# mainboard.net
KiCad netlist of a schematic drawn in EAGLE
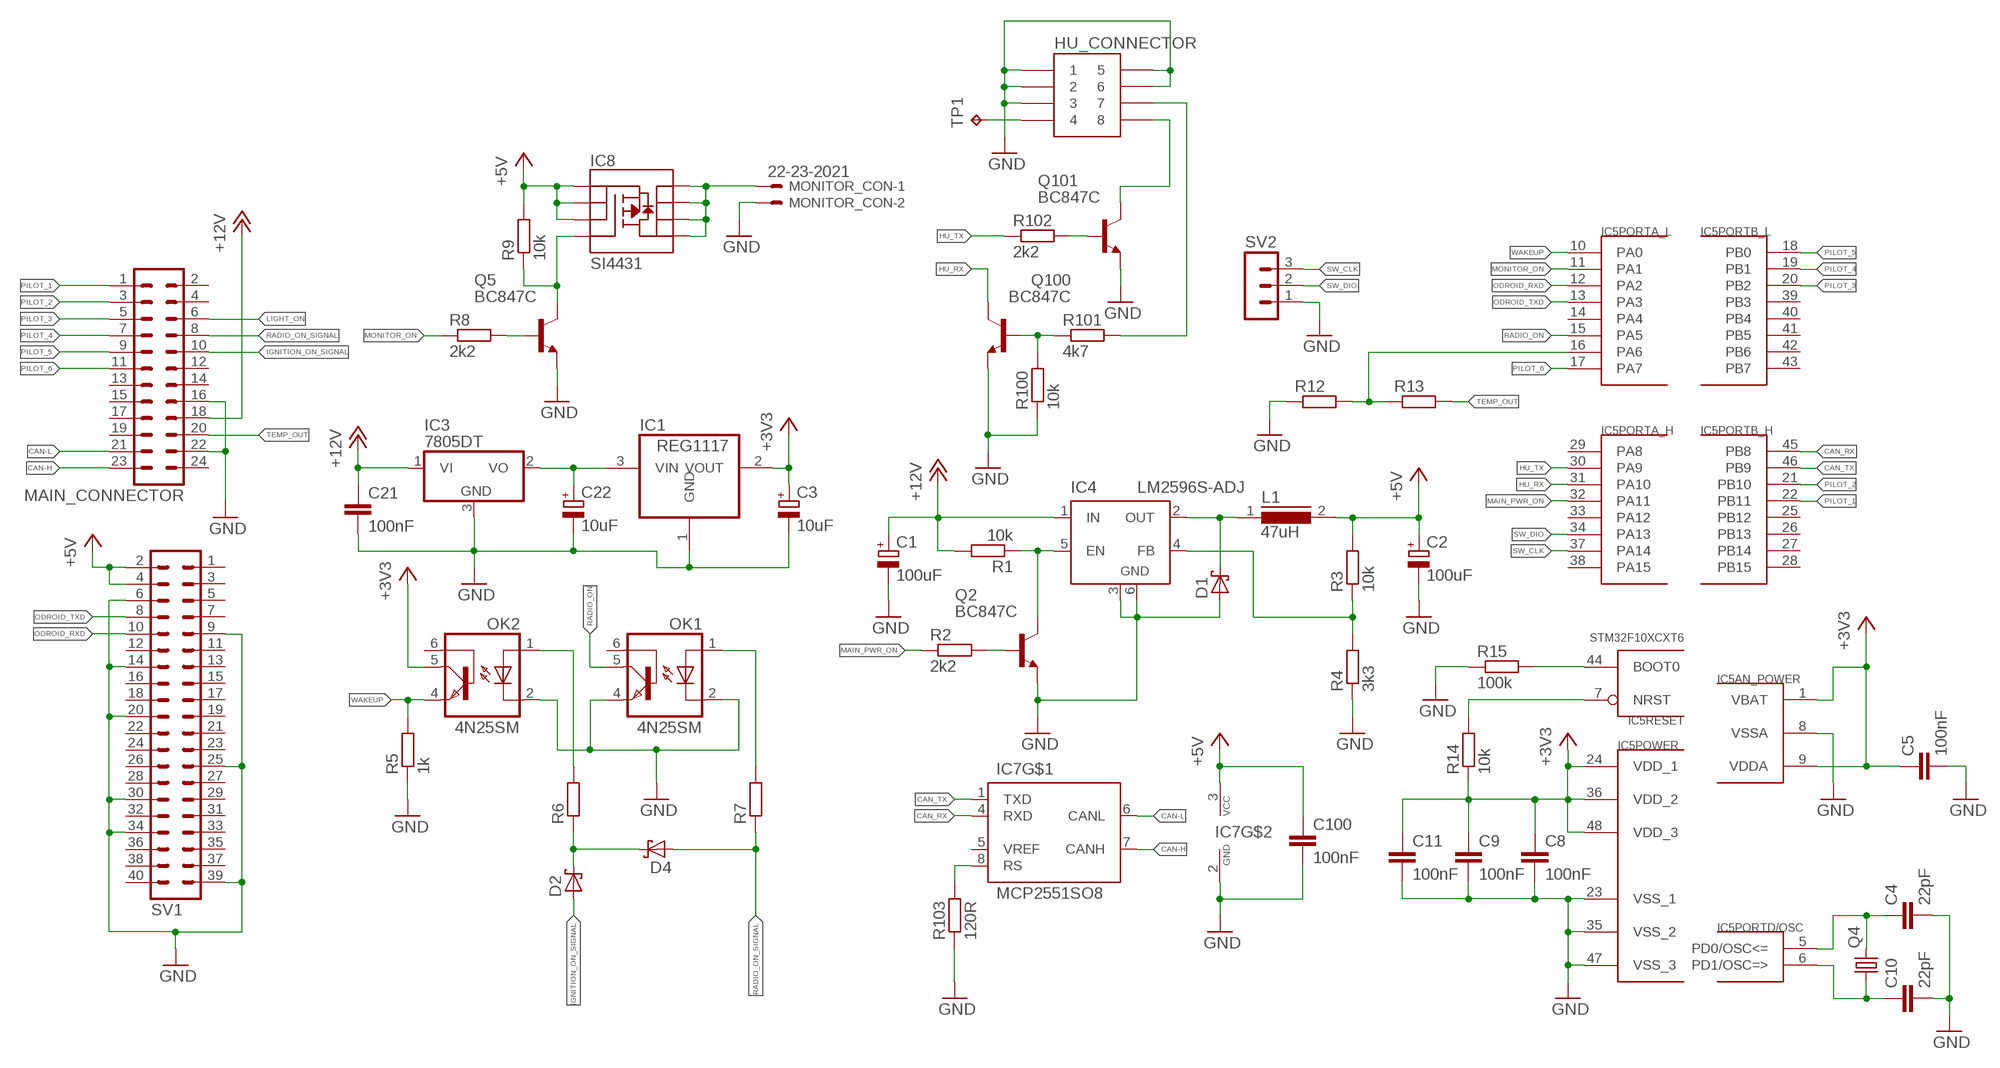
[diagram p0: schematic, sheet 1]

(export (version "E")
  (design (tool "Eeschema 10.0.6"))
  (components
    (comp (ref "C1")
      (value "100uF")
      (footprint "eagle-import:153CLV-0807")
      (libsource (lib "eagle-import") (part "CPOL-EU153CLV-0807"))
    )
    (comp (ref "C2")
      (value "100uF")
      (footprint "eagle-import:153CLV-0807")
      (libsource (lib "eagle-import") (part "CPOL-EU153CLV-0807"))
    )
    (comp (ref "C3")
      (value "10uF")
      (footprint "eagle-import:SMC_A")
      (libsource (lib "eagle-import") (part "CPOL-EUSMCA"))
    )
    (comp (ref "C4")
      (value "22pF")
      (footprint "eagle-import:C0805")
      (libsource (lib "eagle-import") (part "C-EUC0805"))
    )
    (comp (ref "C5")
      (value "100nF")
      (footprint "eagle-import:C0603")
      (libsource (lib "eagle-import") (part "C-EUC0603"))
    )
    (comp (ref "C8")
      (value "100nF")
      (footprint "eagle-import:C0805")
      (libsource (lib "eagle-import") (part "C-EUC0805"))
    )
    (comp (ref "C9")
      (value "100nF")
      (footprint "eagle-import:C0805")
      (libsource (lib "eagle-import") (part "C-EUC0805"))
    )
    (comp (ref "C10")
      (value "22pF")
      (footprint "eagle-import:C0805")
      (libsource (lib "eagle-import") (part "C-EUC0805"))
    )
    (comp (ref "C11")
      (value "100nF")
      (footprint "eagle-import:C0805")
      (libsource (lib "eagle-import") (part "C-EUC0805"))
    )
    (comp (ref "C21")
      (value "100nF")
      (footprint "eagle-import:C0805")
      (libsource (lib "eagle-import") (part "C-EUC0805"))
    )
    (comp (ref "C22")
      (value "10uF")
      (footprint "eagle-import:SMC_A")
      (libsource (lib "eagle-import") (part "CPOL-EUSMCA"))
    )
    (comp (ref "C100")
      (value "100nF")
      (footprint "eagle-import:C0805")
      (libsource (lib "eagle-import") (part "C-EUC0805"))
    )
    (comp (ref "D1")
      (value "SCHOTTKY-DIODESMD")
      (footprint "eagle-import:SMB")
      (libsource (lib "eagle-import") (part "SCHOTTKY-DIODESMD"))
    )
    (comp (ref "D2")
      (value "SCHOTTKY-DIODESMD")
      (footprint "eagle-import:SMB")
      (libsource (lib "eagle-import") (part "SCHOTTKY-DIODESMD"))
    )
    (comp (ref "D4")
      (value "SCHOTTKY-DIODESMD")
      (footprint "eagle-import:SMB")
      (libsource (lib "eagle-import") (part "SCHOTTKY-DIODESMD"))
    )
    (comp (ref "HU_CONNECTOR")
      (value "MRX56908CV")
      (footprint "eagle-import:MRX56908")
      (libsource (lib "eagle-import") (part "MRX56908CV"))
    )
    (comp (ref "IC1")
      (value "REG1117")
      (footprint "eagle-import:SOT223")
      (libsource (lib "eagle-import") (part "REG1117"))
    )
    (comp (ref "IC3")
      (value "7805DT")
      (footprint "eagle-import:TO252")
      (libsource (lib "eagle-import") (part "78DT05"))
    )
    (comp (ref "IC4")
      (value "LM2596S-ADJ")
      (footprint "eagle-import:TO263-5")
      (libsource (lib "eagle-import") (part "LM2596S"))
    )
    (comp (ref "IC5")
      (value "STM32F10XCXT6")
      (footprint "eagle-import:TQFP48")
      (libsource (lib "eagle-import") (part "STM32F10XCXT6"))
    )
    (comp (ref "IC7")
      (value "MCP2551SO8")
      (footprint "eagle-import:SO08")
      (libsource (lib "eagle-import") (part "MCP2551SO8"))
    )
    (comp (ref "IC8")
      (value "SI4431")
      (footprint "eagle-import:SO08")
      (libsource (lib "eagle-import") (part "MOSFET-PCHANNEL-SOIC8SOIC8"))
    )
    (comp (ref "L1")
      (value "47uH")
      (footprint "eagle-import:DR125")
      (libsource (lib "eagle-import") (part "DR125"))
    )
    (comp (ref "MAIN_CONNECTOR")
      (value "MA12-2")
      (footprint "eagle-import:MA12-2")
      (libsource (lib "eagle-import") (part "MA12-2"))
    )
    (comp (ref "MONITOR_CON")
      (value "22-23-2021")
      (footprint "eagle-import:22-23-2021")
      (libsource (lib "eagle-import") (part "22-23-2021"))
    )
    (comp (ref "OK1")
      (value "4N25SM")
      (footprint "eagle-import:DIL6-SMD")
      (libsource (lib "eagle-import") (part "4N?MS25"))
    )
    (comp (ref "OK2")
      (value "4N25SM")
      (footprint "eagle-import:DIL6-SMD")
      (libsource (lib "eagle-import") (part "4N?MS25"))
    )
    (comp (ref "Q2")
      (value "BC847C")
      (footprint "eagle-import:SOT23-BEC")
      (libsource (lib "eagle-import") (part "-NPN-SOT23-BECBC847C"))
    )
    (comp (ref "Q4")
      (value "CRYSTALHC49UP")
      (footprint "eagle-import:HC49UP")
      (libsource (lib "eagle-import") (part "CRYSTALHC49UP"))
    )
    (comp (ref "Q5")
      (value "BC847C")
      (footprint "eagle-import:SOT23-BEC")
      (libsource (lib "eagle-import") (part "-NPN-SOT23-BECBC847C"))
    )
    (comp (ref "Q100")
      (value "BC847C")
      (footprint "eagle-import:SOT23-BEC")
      (libsource (lib "eagle-import") (part "-NPN-SOT23-BECBC847C"))
    )
    (comp (ref "Q101")
      (value "BC847C")
      (footprint "eagle-import:SOT23-BEC")
      (libsource (lib "eagle-import") (part "-NPN-SOT23-BECBC847C"))
    )
    (comp (ref "R1")
      (value "10k")
      (footprint "eagle-import:M0805")
      (libsource (lib "eagle-import") (part "R-EU_M0805"))
    )
    (comp (ref "R2")
      (value "2k2")
      (footprint "eagle-import:M0805")
      (libsource (lib "eagle-import") (part "R-EU_M0805"))
    )
    (comp (ref "R3")
      (value "10k")
      (footprint "eagle-import:M0805")
      (libsource (lib "eagle-import") (part "R-EU_M0805"))
    )
    (comp (ref "R4")
      (value "3k3")
      (footprint "eagle-import:M0805")
      (libsource (lib "eagle-import") (part "R-EU_M0805"))
    )
    (comp (ref "R5")
      (value "1k")
      (footprint "eagle-import:M0805")
      (libsource (lib "eagle-import") (part "R-EU_M0805"))
    )
    (comp (ref "R6")
      (value "R-EU_M0805")
      (footprint "eagle-import:M0805")
      (libsource (lib "eagle-import") (part "R-EU_M0805"))
    )
    (comp (ref "R7")
      (value "R-EU_M0805")
      (footprint "eagle-import:M0805")
      (libsource (lib "eagle-import") (part "R-EU_M0805"))
    )
    (comp (ref "R8")
      (value "2k2")
      (footprint "eagle-import:M0805")
      (libsource (lib "eagle-import") (part "R-EU_M0805"))
    )
    (comp (ref "R9")
      (value "10k")
      (footprint "eagle-import:M0805")
      (libsource (lib "eagle-import") (part "R-EU_M0805"))
    )
    (comp (ref "R12")
      (value "R-EU_M0805")
      (footprint "eagle-import:M0805")
      (libsource (lib "eagle-import") (part "R-EU_M0805"))
    )
    (comp (ref "R13")
      (value "R-EU_M0805")
      (footprint "eagle-import:M0805")
      (libsource (lib "eagle-import") (part "R-EU_M0805"))
    )
    (comp (ref "R14")
      (value "10k")
      (footprint "eagle-import:M0805")
      (libsource (lib "eagle-import") (part "R-EU_M0805"))
    )
    (comp (ref "R15")
      (value "100k")
      (footprint "eagle-import:M0805")
      (libsource (lib "eagle-import") (part "R-EU_M0805"))
    )
    (comp (ref "R100")
      (value "10k")
      (footprint "eagle-import:M0805")
      (libsource (lib "eagle-import") (part "R-EU_M0805"))
    )
    (comp (ref "R101")
      (value "4k7")
      (footprint "eagle-import:M0805")
      (libsource (lib "eagle-import") (part "R-EU_M0805"))
    )
    (comp (ref "R102")
      (value "2k2")
      (footprint "eagle-import:M0805")
      (libsource (lib "eagle-import") (part "R-EU_M0805"))
    )
    (comp (ref "R103")
      (value "120R")
      (footprint "eagle-import:R0805")
      (libsource (lib "eagle-import") (part "resistor_R-EU_R0805"))
    )
    (comp (ref "SV1")
      (value "MA20-2")
      (footprint "eagle-import:MA20-2")
      (libsource (lib "eagle-import") (part "MA20-2"))
    )
    (comp (ref "SV2")
      (value "MA03-1")
      (footprint "eagle-import:MA03-1")
      (libsource (lib "eagle-import") (part "MA03-1"))
    )
    (comp (ref "TP1")
      (value "TPPAD1-13")
      (footprint "eagle-import:P1-13")
      (libsource (lib "eagle-import") (part "TPPAD1-13"))
    )
  )
  (nets
    (net (code "1") (name "+3V3") (class "Default")
      (node (ref "C11") (pin "1") (pinfunction "1_1") (pintype "passive"))
      (node (ref "C3") (pin "+") (pinfunction "+_+") (pintype "passive"))
      (node (ref "C5") (pin "1") (pinfunction "1_1") (pintype "passive"))
      (node (ref "C8") (pin "1") (pinfunction "1_1") (pintype "passive"))
      (node (ref "C9") (pin "1") (pinfunction "1_1") (pintype "passive"))
      (node (ref "IC1") (pin "2") (pinfunction "VOUT_2") (pintype "output"))
      (node (ref "IC5") (pin "1") (pinfunction "VBAT_1") (pintype "power_in"))
      (node (ref "IC5") (pin "24") (pinfunction "VDD_1_24") (pintype "power_in"))
      (node (ref "IC5") (pin "36") (pinfunction "VDD_2_36") (pintype "power_in"))
      (node (ref "IC5") (pin "48") (pinfunction "VDD_3_48") (pintype "power_in"))
      (node (ref "IC5") (pin "9") (pinfunction "VDDA_9") (pintype "power_in"))
      (node (ref "OK2") (pin "5") (pinfunction "COL_5") (pintype "passive"))
      (node (ref "R14") (pin "1") (pinfunction "1_1") (pintype "passive"))
    )
    (net (code "2") (name "+5V") (class "Default")
      (node (ref "C100") (pin "1") (pinfunction "1_1") (pintype "passive"))
      (node (ref "C2") (pin "+") (pinfunction "+_+") (pintype "passive"))
      (node (ref "IC7") (pin "3") (pinfunction "VCC_3") (pintype "power_in"))
      (node (ref "IC8") (pin "1") (pinfunction "S_1") (pintype "bidirectional"))
      (node (ref "IC8") (pin "2") (pinfunction "S_2") (pintype "bidirectional"))
      (node (ref "IC8") (pin "3") (pinfunction "S_3") (pintype "bidirectional"))
      (node (ref "L1") (pin "2") (pinfunction "2_2") (pintype "passive"))
      (node (ref "R3") (pin "2") (pinfunction "2_2") (pintype "passive"))
      (node (ref "R9") (pin "2") (pinfunction "2_2") (pintype "passive"))
      (node (ref "SV1") (pin "2") (pinfunction "2_2") (pintype "passive"))
      (node (ref "SV1") (pin "4") (pinfunction "4_4") (pintype "passive"))
    )
    (net (code "3") (name "+12V") (class "Default")
      (node (ref "C1") (pin "+") (pinfunction "+_+") (pintype "passive"))
      (node (ref "C21") (pin "1") (pinfunction "1_1") (pintype "passive"))
      (node (ref "IC3") (pin "1") (pinfunction "VI_1") (pintype "input"))
      (node (ref "IC4") (pin "1") (pinfunction "IN_1") (pintype "input"))
      (node (ref "MAIN_CONNECTOR") (pin "18") (pinfunction "18_18") (pintype "passive"))
      (node (ref "R1") (pin "2") (pinfunction "2_2") (pintype "passive"))
    )
    (net (code "4") (name "CAN-H") (class "Default")
      (node (ref "IC7") (pin "7") (pinfunction "CANH_7") (pintype "bidirectional"))
      (node (ref "MAIN_CONNECTOR") (pin "23") (pinfunction "23_23") (pintype "passive"))
    )
    (net (code "5") (name "CAN-L") (class "Default")
      (node (ref "IC7") (pin "6") (pinfunction "CANL_6") (pintype "bidirectional"))
      (node (ref "MAIN_CONNECTOR") (pin "21") (pinfunction "21_21") (pintype "passive"))
    )
    (net (code "6") (name "CAN_RX") (class "Default")
      (node (ref "IC5") (pin "45") (pinfunction "PB8_45") (pintype "bidirectional"))
      (node (ref "IC7") (pin "4") (pinfunction "RXD_4") (pintype "bidirectional"))
    )
    (net (code "7") (name "CAN_TX") (class "Default")
      (node (ref "IC5") (pin "46") (pinfunction "PB9_46") (pintype "bidirectional"))
      (node (ref "IC7") (pin "1") (pinfunction "TXD_1") (pintype "bidirectional"))
    )
    (net (code "8") (name "GND") (class "Default")
      (node (ref "C1") (pin "-") (pinfunction "-_-") (pintype "passive"))
      (node (ref "C10") (pin "2") (pinfunction "2_2") (pintype "passive"))
      (node (ref "C100") (pin "2") (pinfunction "2_2") (pintype "passive"))
      (node (ref "C11") (pin "2") (pinfunction "2_2") (pintype "passive"))
      (node (ref "C2") (pin "-") (pinfunction "-_-") (pintype "passive"))
      (node (ref "C21") (pin "2") (pinfunction "2_2") (pintype "passive"))
      (node (ref "C22") (pin "-") (pinfunction "-_-") (pintype "passive"))
      (node (ref "C3") (pin "-") (pinfunction "-_-") (pintype "passive"))
      (node (ref "C4") (pin "2") (pinfunction "2_2") (pintype "passive"))
      (node (ref "C5") (pin "2") (pinfunction "2_2") (pintype "passive"))
      (node (ref "C8") (pin "2") (pinfunction "2_2") (pintype "passive"))
      (node (ref "C9") (pin "2") (pinfunction "2_2") (pintype "passive"))
      (node (ref "D1") (pin "A") (pinfunction "A_A") (pintype "passive"))
      (node (ref "HU_CONNECTOR") (pin "P1") (pinfunction "1_P1") (pintype "bidirectional"))
      (node (ref "HU_CONNECTOR") (pin "P2") (pinfunction "2_P2") (pintype "bidirectional"))
      (node (ref "HU_CONNECTOR") (pin "P3") (pinfunction "3_P3") (pintype "bidirectional"))
      (node (ref "HU_CONNECTOR") (pin "P5") (pinfunction "5_P5") (pintype "bidirectional"))
      (node (ref "HU_CONNECTOR") (pin "P6") (pinfunction "6_P6") (pintype "bidirectional"))
      (node (ref "IC1") (pin "1") (pinfunction "GND_1") (pintype "power_in"))
      (node (ref "IC3") (pin "3") (pinfunction "GND_3") (pintype "passive"))
      (node (ref "IC4") (pin "3") (pinfunction "GND_3") (pintype "power_in"))
      (node (ref "IC4") (pin "6") (pinfunction "GND_6") (pintype "power_in"))
      (node (ref "IC5") (pin "23") (pinfunction "VSS_1_23") (pintype "power_in"))
      (node (ref "IC5") (pin "35") (pinfunction "VSS_2_35") (pintype "power_in"))
      (node (ref "IC5") (pin "47") (pinfunction "VSS_3_47") (pintype "power_in"))
      (node (ref "IC5") (pin "8") (pinfunction "VSSA_8") (pintype "power_in"))
      (node (ref "IC7") (pin "2") (pinfunction "GND_2") (pintype "power_in"))
      (node (ref "MAIN_CONNECTOR") (pin "16") (pinfunction "16_16") (pintype "passive"))
      (node (ref "MAIN_CONNECTOR") (pin "22") (pinfunction "22_22") (pintype "passive"))
      (node (ref "MONITOR_CON") (pin "2") (pinfunction "S_2") (pintype "passive"))
      (node (ref "OK1") (pin "2") (pinfunction "C_2") (pintype "passive"))
      (node (ref "OK1") (pin "4") (pinfunction "EMI_4") (pintype "passive"))
      (node (ref "OK2") (pin "2") (pinfunction "C_2") (pintype "passive"))
      (node (ref "Q100") (pin "E") (pinfunction "E_E") (pintype "passive"))
      (node (ref "Q101") (pin "E") (pinfunction "E_E") (pintype "passive"))
      (node (ref "Q2") (pin "E") (pinfunction "E_E") (pintype "passive"))
      (node (ref "Q5") (pin "E") (pinfunction "E_E") (pintype "passive"))
      (node (ref "R100") (pin "1") (pinfunction "1_1") (pintype "passive"))
      (node (ref "R103") (pin "1") (pinfunction "1_1") (pintype "passive"))
      (node (ref "R12") (pin "1") (pinfunction "1_1") (pintype "passive"))
      (node (ref "R15") (pin "1") (pinfunction "1_1") (pintype "passive"))
      (node (ref "R4") (pin "1") (pinfunction "1_1") (pintype "passive"))
      (node (ref "R5") (pin "1") (pinfunction "1_1") (pintype "passive"))
      (node (ref "SV1") (pin "14") (pinfunction "14_14") (pintype "passive"))
      (node (ref "SV1") (pin "20") (pinfunction "20_20") (pintype "passive"))
      (node (ref "SV1") (pin "25") (pinfunction "25_25") (pintype "passive"))
      (node (ref "SV1") (pin "30") (pinfunction "30_30") (pintype "passive"))
      (node (ref "SV1") (pin "34") (pinfunction "34_34") (pintype "passive"))
      (node (ref "SV1") (pin "39") (pinfunction "39_39") (pintype "passive"))
      (node (ref "SV1") (pin "6") (pinfunction "6_6") (pintype "passive"))
      (node (ref "SV1") (pin "9") (pinfunction "9_9") (pintype "passive"))
      (node (ref "SV2") (pin "1") (pinfunction "1_1") (pintype "passive"))
    )
    (net (code "9") (name "HU_RX") (class "Default")
      (node (ref "IC5") (pin "31") (pinfunction "PA10_31") (pintype "bidirectional"))
      (node (ref "Q100") (pin "C") (pinfunction "C_C") (pintype "passive"))
    )
    (net (code "10") (name "HU_TX") (class "Default")
      (node (ref "IC5") (pin "30") (pinfunction "PA9_30") (pintype "bidirectional"))
      (node (ref "R102") (pin "1") (pinfunction "1_1") (pintype "passive"))
    )
    (net (code "11") (name "IGNITION_ON_SIGNAL") (class "Default")
      (node (ref "D2") (pin "A") (pinfunction "A_A") (pintype "passive"))
      (node (ref "MAIN_CONNECTOR") (pin "10") (pinfunction "10_10") (pintype "passive"))
    )
    (net (code "12") (name "LIGHT_ON") (class "Default")
      (node (ref "MAIN_CONNECTOR") (pin "6") (pinfunction "6_6") (pintype "passive"))
    )
    (net (code "13") (name "MAIN_PWR_ON") (class "Default")
      (node (ref "IC5") (pin "32") (pinfunction "PA11_32") (pintype "bidirectional"))
      (node (ref "R2") (pin "1") (pinfunction "1_1") (pintype "passive"))
    )
    (net (code "14") (name "MONITOR_ON") (class "Default")
      (node (ref "IC5") (pin "11") (pinfunction "PA1_11") (pintype "bidirectional"))
      (node (ref "R8") (pin "1") (pinfunction "1_1") (pintype "passive"))
    )
    (net (code "15") (name "Net-(D2-PadC)") (class "Default")
      (node (ref "D2") (pin "C") (pinfunction "C_C") (pintype "passive"))
      (node (ref "D4") (pin "C") (pinfunction "C_C") (pintype "passive"))
      (node (ref "R6") (pin "1") (pinfunction "1_1") (pintype "passive"))
    )
    (net (code "16") (name "Net-(HU_CONNECTOR-4)") (class "Default")
      (node (ref "HU_CONNECTOR") (pin "P4") (pinfunction "4_P4") (pintype "bidirectional"))
      (node (ref "TP1") (pin "TP") (pinfunction "TP_TP") (pintype "input"))
    )
    (net (code "17") (name "Net-(HU_CONNECTOR-7)") (class "Default")
      (node (ref "HU_CONNECTOR") (pin "P7") (pinfunction "7_P7") (pintype "bidirectional"))
      (node (ref "R101") (pin "2") (pinfunction "2_2") (pintype "passive"))
    )
    (net (code "18") (name "Net-(HU_CONNECTOR-8)") (class "Default")
      (node (ref "HU_CONNECTOR") (pin "P8") (pinfunction "8_P8") (pintype "bidirectional"))
      (node (ref "Q101") (pin "C") (pinfunction "C_C") (pintype "passive"))
    )
    (net (code "19") (name "Net-(IC1-VIN)") (class "Default")
      (node (ref "C22") (pin "+") (pinfunction "+_+") (pintype "passive"))
      (node (ref "IC1") (pin "3") (pinfunction "VIN_3") (pintype "input"))
      (node (ref "IC3") (pin "2") (pinfunction "VO_2") (pintype "passive"))
    )
    (net (code "20") (name "Net-(IC4-EN)") (class "Default")
      (node (ref "IC4") (pin "5") (pinfunction "EN_5") (pintype "input"))
      (node (ref "Q2") (pin "C") (pinfunction "C_C") (pintype "passive"))
      (node (ref "R1") (pin "1") (pinfunction "1_1") (pintype "passive"))
    )
    (net (code "21") (name "Net-(IC4-FB)") (class "Default")
      (node (ref "IC4") (pin "4") (pinfunction "FB_4") (pintype "input"))
      (node (ref "R3") (pin "1") (pinfunction "1_1") (pintype "passive"))
      (node (ref "R4") (pin "2") (pinfunction "2_2") (pintype "passive"))
    )
    (net (code "22") (name "Net-(IC4-OUT)") (class "Default")
      (node (ref "D1") (pin "C") (pinfunction "C_C") (pintype "passive"))
      (node (ref "IC4") (pin "2") (pinfunction "OUT_2") (pintype "output"))
      (node (ref "L1") (pin "1") (pinfunction "1_1") (pintype "passive"))
    )
    (net (code "23") (name "Net-(IC5C-PA6)") (class "Default")
      (node (ref "IC5") (pin "16") (pinfunction "PA6_16") (pintype "bidirectional"))
      (node (ref "R12") (pin "2") (pinfunction "2_2") (pintype "passive"))
      (node (ref "R13") (pin "1") (pinfunction "1_1") (pintype "passive"))
    )
    (net (code "24") (name "Net-(IC5G-PD0{slash}OSC<=)") (class "Default")
      (node (ref "C4") (pin "1") (pinfunction "1_1") (pintype "passive"))
      (node (ref "IC5") (pin "5") (pinfunction "PD0/OSC<=_5") (pintype "bidirectional"))
      (node (ref "Q4") (pin "2") (pinfunction "2_2") (pintype "passive"))
    )
    (net (code "25") (name "Net-(IC5G-PD1{slash}OSC=>)") (class "Default")
      (node (ref "C10") (pin "1") (pinfunction "1_1") (pintype "passive"))
      (node (ref "IC5") (pin "6") (pinfunction "PD1/OSC=>_6") (pintype "bidirectional"))
      (node (ref "Q4") (pin "1") (pinfunction "1_1") (pintype "passive"))
    )
    (net (code "26") (name "Net-(IC5I-BOOT0)") (class "Default")
      (node (ref "IC5") (pin "44") (pinfunction "BOOT0_44") (pintype "input"))
      (node (ref "R15") (pin "2") (pinfunction "2_2") (pintype "passive"))
    )
    (net (code "27") (name "Net-(IC5I-NRST)") (class "Default")
      (node (ref "IC5") (pin "7") (pinfunction "NRST_7") (pintype "input"))
      (node (ref "R14") (pin "2") (pinfunction "2_2") (pintype "passive"))
    )
    (net (code "28") (name "Net-(IC7A-RS)") (class "Default")
      (node (ref "IC7") (pin "8") (pinfunction "RS_8") (pintype "bidirectional"))
      (node (ref "R103") (pin "2") (pinfunction "2_2") (pintype "passive"))
    )
    (net (code "29") (name "Net-(IC8-G)") (class "Default")
      (node (ref "IC8") (pin "4") (pinfunction "G_4") (pintype "bidirectional"))
      (node (ref "Q5") (pin "C") (pinfunction "C_C") (pintype "passive"))
      (node (ref "R9") (pin "1") (pinfunction "1_1") (pintype "passive"))
    )
    (net (code "30") (name "Net-(MONITOR_CONA-S)") (class "Default")
      (node (ref "IC8") (pin "5") (pinfunction "D_5") (pintype "bidirectional"))
      (node (ref "IC8") (pin "6") (pinfunction "D_6") (pintype "bidirectional"))
      (node (ref "IC8") (pin "7") (pinfunction "D_7") (pintype "bidirectional"))
      (node (ref "IC8") (pin "8") (pinfunction "D_8") (pintype "bidirectional"))
      (node (ref "MONITOR_CON") (pin "1") (pinfunction "S_1") (pintype "passive"))
    )
    (net (code "31") (name "Net-(OK1-A)") (class "Default")
      (node (ref "OK1") (pin "1") (pinfunction "A_1") (pintype "passive"))
      (node (ref "R7") (pin "2") (pinfunction "2_2") (pintype "passive"))
    )
    (net (code "32") (name "Net-(OK2-A)") (class "Default")
      (node (ref "OK2") (pin "1") (pinfunction "A_1") (pintype "passive"))
      (node (ref "R6") (pin "2") (pinfunction "2_2") (pintype "passive"))
    )
    (net (code "33") (name "Net-(Q2-PadB)") (class "Default")
      (node (ref "Q2") (pin "B") (pinfunction "B_B") (pintype "passive"))
      (node (ref "R2") (pin "2") (pinfunction "2_2") (pintype "passive"))
    )
    (net (code "34") (name "Net-(Q5-PadB)") (class "Default")
      (node (ref "Q5") (pin "B") (pinfunction "B_B") (pintype "passive"))
      (node (ref "R8") (pin "2") (pinfunction "2_2") (pintype "passive"))
    )
    (net (code "35") (name "Net-(Q100-PadB)") (class "Default")
      (node (ref "Q100") (pin "B") (pinfunction "B_B") (pintype "passive"))
      (node (ref "R100") (pin "2") (pinfunction "2_2") (pintype "passive"))
      (node (ref "R101") (pin "1") (pinfunction "1_1") (pintype "passive"))
    )
    (net (code "36") (name "Net-(Q101-PadB)") (class "Default")
      (node (ref "Q101") (pin "B") (pinfunction "B_B") (pintype "passive"))
      (node (ref "R102") (pin "2") (pinfunction "2_2") (pintype "passive"))
    )
    (net (code "37") (name "ODROID_RXD") (class "Default")
      (node (ref "IC5") (pin "12") (pinfunction "PA2_12") (pintype "bidirectional"))
      (node (ref "SV1") (pin "10") (pinfunction "10_10") (pintype "passive"))
    )
    (net (code "38") (name "ODROID_TXD") (class "Default")
      (node (ref "IC5") (pin "13") (pinfunction "PA3_13") (pintype "bidirectional"))
      (node (ref "SV1") (pin "8") (pinfunction "8_8") (pintype "passive"))
    )
    (net (code "39") (name "PILOT_1") (class "Default")
      (node (ref "IC5") (pin "22") (pinfunction "PB11_22") (pintype "bidirectional"))
      (node (ref "MAIN_CONNECTOR") (pin "1") (pinfunction "1_1") (pintype "passive"))
    )
    (net (code "40") (name "PILOT_2") (class "Default")
      (node (ref "IC5") (pin "21") (pinfunction "PB10_21") (pintype "bidirectional"))
      (node (ref "MAIN_CONNECTOR") (pin "3") (pinfunction "3_3") (pintype "passive"))
    )
    (net (code "41") (name "PILOT_3") (class "Default")
      (node (ref "IC5") (pin "20") (pinfunction "PB2_20") (pintype "bidirectional"))
      (node (ref "MAIN_CONNECTOR") (pin "5") (pinfunction "5_5") (pintype "passive"))
    )
    (net (code "42") (name "PILOT_4") (class "Default")
      (node (ref "IC5") (pin "19") (pinfunction "PB1_19") (pintype "bidirectional"))
      (node (ref "MAIN_CONNECTOR") (pin "7") (pinfunction "7_7") (pintype "passive"))
    )
    (net (code "43") (name "PILOT_5") (class "Default")
      (node (ref "IC5") (pin "18") (pinfunction "PB0_18") (pintype "bidirectional"))
      (node (ref "MAIN_CONNECTOR") (pin "9") (pinfunction "9_9") (pintype "passive"))
    )
    (net (code "44") (name "PILOT_6") (class "Default")
      (node (ref "IC5") (pin "17") (pinfunction "PA7_17") (pintype "bidirectional"))
      (node (ref "MAIN_CONNECTOR") (pin "11") (pinfunction "11_11") (pintype "passive"))
    )
    (net (code "45") (name "RADIO_ON") (class "Default")
      (node (ref "IC5") (pin "15") (pinfunction "PA5_15") (pintype "bidirectional"))
      (node (ref "OK1") (pin "5") (pinfunction "COL_5") (pintype "passive"))
    )
    (net (code "46") (name "RADIO_ON_SIGNAL") (class "Default")
      (node (ref "D4") (pin "A") (pinfunction "A_A") (pintype "passive"))
      (node (ref "MAIN_CONNECTOR") (pin "8") (pinfunction "8_8") (pintype "passive"))
      (node (ref "R7") (pin "1") (pinfunction "1_1") (pintype "passive"))
    )
    (net (code "47") (name "SW_CLK") (class "Default")
      (node (ref "IC5") (pin "37") (pinfunction "PA14_37") (pintype "bidirectional"))
      (node (ref "SV2") (pin "3") (pinfunction "3_3") (pintype "passive"))
    )
    (net (code "48") (name "SW_DIO") (class "Default")
      (node (ref "IC5") (pin "34") (pinfunction "PA13_34") (pintype "bidirectional"))
      (node (ref "SV2") (pin "2") (pinfunction "2_2") (pintype "passive"))
    )
    (net (code "49") (name "TEMP_OUT") (class "Default")
      (node (ref "MAIN_CONNECTOR") (pin "20") (pinfunction "20_20") (pintype "passive"))
      (node (ref "R13") (pin "2") (pinfunction "2_2") (pintype "passive"))
    )
    (net (code "50") (name "WAKEUP") (class "Default")
      (node (ref "IC5") (pin "10") (pinfunction "PA0_10") (pintype "bidirectional"))
      (node (ref "OK2") (pin "4") (pinfunction "EMI_4") (pintype "passive"))
      (node (ref "R5") (pin "2") (pinfunction "2_2") (pintype "passive"))
    )
    (net (code "51") (name "unconnected-(IC5B-PA8-Pad29)") (class "Default")
      (node (ref "IC5") (pin "29") (pinfunction "PA8_29") (pintype "bidirectional"))
    )
    (net (code "52") (name "unconnected-(IC5B-PA12-Pad33)") (class "Default")
      (node (ref "IC5") (pin "33") (pinfunction "PA12_33") (pintype "bidirectional"))
    )
    (net (code "53") (name "unconnected-(IC5B-PA15-Pad38)") (class "Default")
      (node (ref "IC5") (pin "38") (pinfunction "PA15_38") (pintype "bidirectional"))
    )
    (net (code "54") (name "unconnected-(IC5C-PA4-Pad14)") (class "Default")
      (node (ref "IC5") (pin "14") (pinfunction "PA4_14") (pintype "bidirectional"))
    )
    (net (code "55") (name "unconnected-(IC5D-PB12-Pad25)") (class "Default")
      (node (ref "IC5") (pin "25") (pinfunction "PB12_25") (pintype "bidirectional"))
    )
    (net (code "56") (name "unconnected-(IC5D-PB13-Pad26)") (class "Default")
      (node (ref "IC5") (pin "26") (pinfunction "PB13_26") (pintype "bidirectional"))
    )
    (net (code "57") (name "unconnected-(IC5D-PB14-Pad27)") (class "Default")
      (node (ref "IC5") (pin "27") (pinfunction "PB14_27") (pintype "bidirectional"))
    )
    (net (code "58") (name "unconnected-(IC5D-PB15-Pad28)") (class "Default")
      (node (ref "IC5") (pin "28") (pinfunction "PB15_28") (pintype "bidirectional"))
    )
    (net (code "59") (name "unconnected-(IC5E-PB3-Pad39)") (class "Default")
      (node (ref "IC5") (pin "39") (pinfunction "PB3_39") (pintype "bidirectional"))
    )
    (net (code "60") (name "unconnected-(IC5E-PB4-Pad40)") (class "Default")
      (node (ref "IC5") (pin "40") (pinfunction "PB4_40") (pintype "bidirectional"))
    )
    (net (code "61") (name "unconnected-(IC5E-PB5-Pad41)") (class "Default")
      (node (ref "IC5") (pin "41") (pinfunction "PB5_41") (pintype "bidirectional"))
    )
    (net (code "62") (name "unconnected-(IC5E-PB6-Pad42)") (class "Default")
      (node (ref "IC5") (pin "42") (pinfunction "PB6_42") (pintype "bidirectional"))
    )
    (net (code "63") (name "unconnected-(IC5E-PB7-Pad43)") (class "Default")
      (node (ref "IC5") (pin "43") (pinfunction "PB7_43") (pintype "bidirectional"))
    )
    (net (code "64") (name "unconnected-(IC7A-VREF-Pad5)") (class "Default")
      (node (ref "IC7") (pin "5") (pinfunction "VREF_5") (pintype "bidirectional"))
    )
    (net (code "65") (name "unconnected-(MAIN_CONNECTOR-Pad2)") (class "Default")
      (node (ref "MAIN_CONNECTOR") (pin "2") (pinfunction "2_2") (pintype "passive"))
    )
    (net (code "66") (name "unconnected-(MAIN_CONNECTOR-Pad4)") (class "Default")
      (node (ref "MAIN_CONNECTOR") (pin "4") (pinfunction "4_4") (pintype "passive"))
    )
    (net (code "67") (name "unconnected-(MAIN_CONNECTOR-Pad12)") (class "Default")
      (node (ref "MAIN_CONNECTOR") (pin "12") (pinfunction "12_12") (pintype "passive"))
    )
    (net (code "68") (name "unconnected-(MAIN_CONNECTOR-Pad13)") (class "Default")
      (node (ref "MAIN_CONNECTOR") (pin "13") (pinfunction "13_13") (pintype "passive"))
    )
    (net (code "69") (name "unconnected-(MAIN_CONNECTOR-Pad14)") (class "Default")
      (node (ref "MAIN_CONNECTOR") (pin "14") (pinfunction "14_14") (pintype "passive"))
    )
    (net (code "70") (name "unconnected-(MAIN_CONNECTOR-Pad15)") (class "Default")
      (node (ref "MAIN_CONNECTOR") (pin "15") (pinfunction "15_15") (pintype "passive"))
    )
    (net (code "71") (name "unconnected-(MAIN_CONNECTOR-Pad17)") (class "Default")
      (node (ref "MAIN_CONNECTOR") (pin "17") (pinfunction "17_17") (pintype "passive"))
    )
    (net (code "72") (name "unconnected-(MAIN_CONNECTOR-Pad19)") (class "Default")
      (node (ref "MAIN_CONNECTOR") (pin "19") (pinfunction "19_19") (pintype "passive"))
    )
    (net (code "73") (name "unconnected-(MAIN_CONNECTOR-Pad24)") (class "Default")
      (node (ref "MAIN_CONNECTOR") (pin "24") (pinfunction "24_24") (pintype "passive"))
    )
    (net (code "74") (name "unconnected-(OK1-BAS-Pad6)") (class "Default")
      (node (ref "OK1") (pin "6") (pinfunction "BAS_6") (pintype "passive"))
    )
    (net (code "75") (name "unconnected-(OK2-BAS-Pad6)") (class "Default")
      (node (ref "OK2") (pin "6") (pinfunction "BAS_6") (pintype "passive"))
    )
    (net (code "76") (name "unconnected-(SV1-Pad1)") (class "Default")
      (node (ref "SV1") (pin "1") (pinfunction "1_1") (pintype "passive"))
    )
    (net (code "77") (name "unconnected-(SV1-Pad3)") (class "Default")
      (node (ref "SV1") (pin "3") (pinfunction "3_3") (pintype "passive"))
    )
    (net (code "78") (name "unconnected-(SV1-Pad5)") (class "Default")
      (node (ref "SV1") (pin "5") (pinfunction "5_5") (pintype "passive"))
    )
    (net (code "79") (name "unconnected-(SV1-Pad7)") (class "Default")
      (node (ref "SV1") (pin "7") (pinfunction "7_7") (pintype "passive"))
    )
    (net (code "80") (name "unconnected-(SV1-Pad11)") (class "Default")
      (node (ref "SV1") (pin "11") (pinfunction "11_11") (pintype "passive"))
    )
    (net (code "81") (name "unconnected-(SV1-Pad12)") (class "Default")
      (node (ref "SV1") (pin "12") (pinfunction "12_12") (pintype "passive"))
    )
    (net (code "82") (name "unconnected-(SV1-Pad13)") (class "Default")
      (node (ref "SV1") (pin "13") (pinfunction "13_13") (pintype "passive"))
    )
    (net (code "83") (name "unconnected-(SV1-Pad15)") (class "Default")
      (node (ref "SV1") (pin "15") (pinfunction "15_15") (pintype "passive"))
    )
    (net (code "84") (name "unconnected-(SV1-Pad16)") (class "Default")
      (node (ref "SV1") (pin "16") (pinfunction "16_16") (pintype "passive"))
    )
    (net (code "85") (name "unconnected-(SV1-Pad17)") (class "Default")
      (node (ref "SV1") (pin "17") (pinfunction "17_17") (pintype "passive"))
    )
    (net (code "86") (name "unconnected-(SV1-Pad18)") (class "Default")
      (node (ref "SV1") (pin "18") (pinfunction "18_18") (pintype "passive"))
    )
    (net (code "87") (name "unconnected-(SV1-Pad19)") (class "Default")
      (node (ref "SV1") (pin "19") (pinfunction "19_19") (pintype "passive"))
    )
    (net (code "88") (name "unconnected-(SV1-Pad21)") (class "Default")
      (node (ref "SV1") (pin "21") (pinfunction "21_21") (pintype "passive"))
    )
    (net (code "89") (name "unconnected-(SV1-Pad22)") (class "Default")
      (node (ref "SV1") (pin "22") (pinfunction "22_22") (pintype "passive"))
    )
    (net (code "90") (name "unconnected-(SV1-Pad23)") (class "Default")
      (node (ref "SV1") (pin "23") (pinfunction "23_23") (pintype "passive"))
    )
    (net (code "91") (name "unconnected-(SV1-Pad24)") (class "Default")
      (node (ref "SV1") (pin "24") (pinfunction "24_24") (pintype "passive"))
    )
    (net (code "92") (name "unconnected-(SV1-Pad26)") (class "Default")
      (node (ref "SV1") (pin "26") (pinfunction "26_26") (pintype "passive"))
    )
    (net (code "93") (name "unconnected-(SV1-Pad27)") (class "Default")
      (node (ref "SV1") (pin "27") (pinfunction "27_27") (pintype "passive"))
    )
    (net (code "94") (name "unconnected-(SV1-Pad28)") (class "Default")
      (node (ref "SV1") (pin "28") (pinfunction "28_28") (pintype "passive"))
    )
    (net (code "95") (name "unconnected-(SV1-Pad29)") (class "Default")
      (node (ref "SV1") (pin "29") (pinfunction "29_29") (pintype "passive"))
    )
    (net (code "96") (name "unconnected-(SV1-Pad31)") (class "Default")
      (node (ref "SV1") (pin "31") (pinfunction "31_31") (pintype "passive"))
    )
    (net (code "97") (name "unconnected-(SV1-Pad32)") (class "Default")
      (node (ref "SV1") (pin "32") (pinfunction "32_32") (pintype "passive"))
    )
    (net (code "98") (name "unconnected-(SV1-Pad33)") (class "Default")
      (node (ref "SV1") (pin "33") (pinfunction "33_33") (pintype "passive"))
    )
    (net (code "99") (name "unconnected-(SV1-Pad35)") (class "Default")
      (node (ref "SV1") (pin "35") (pinfunction "35_35") (pintype "passive"))
    )
    (net (code "100") (name "unconnected-(SV1-Pad36)") (class "Default")
      (node (ref "SV1") (pin "36") (pinfunction "36_36") (pintype "passive"))
    )
    (net (code "101") (name "unconnected-(SV1-Pad37)") (class "Default")
      (node (ref "SV1") (pin "37") (pinfunction "37_37") (pintype "passive"))
    )
    (net (code "102") (name "unconnected-(SV1-Pad38)") (class "Default")
      (node (ref "SV1") (pin "38") (pinfunction "38_38") (pintype "passive"))
    )
    (net (code "103") (name "unconnected-(SV1-Pad40)") (class "Default")
      (node (ref "SV1") (pin "40") (pinfunction "40_40") (pintype "passive"))
    )
  )
)
